# USBHUB.net
KiCad netlist of a schematic drawn in EasyEDA Pro
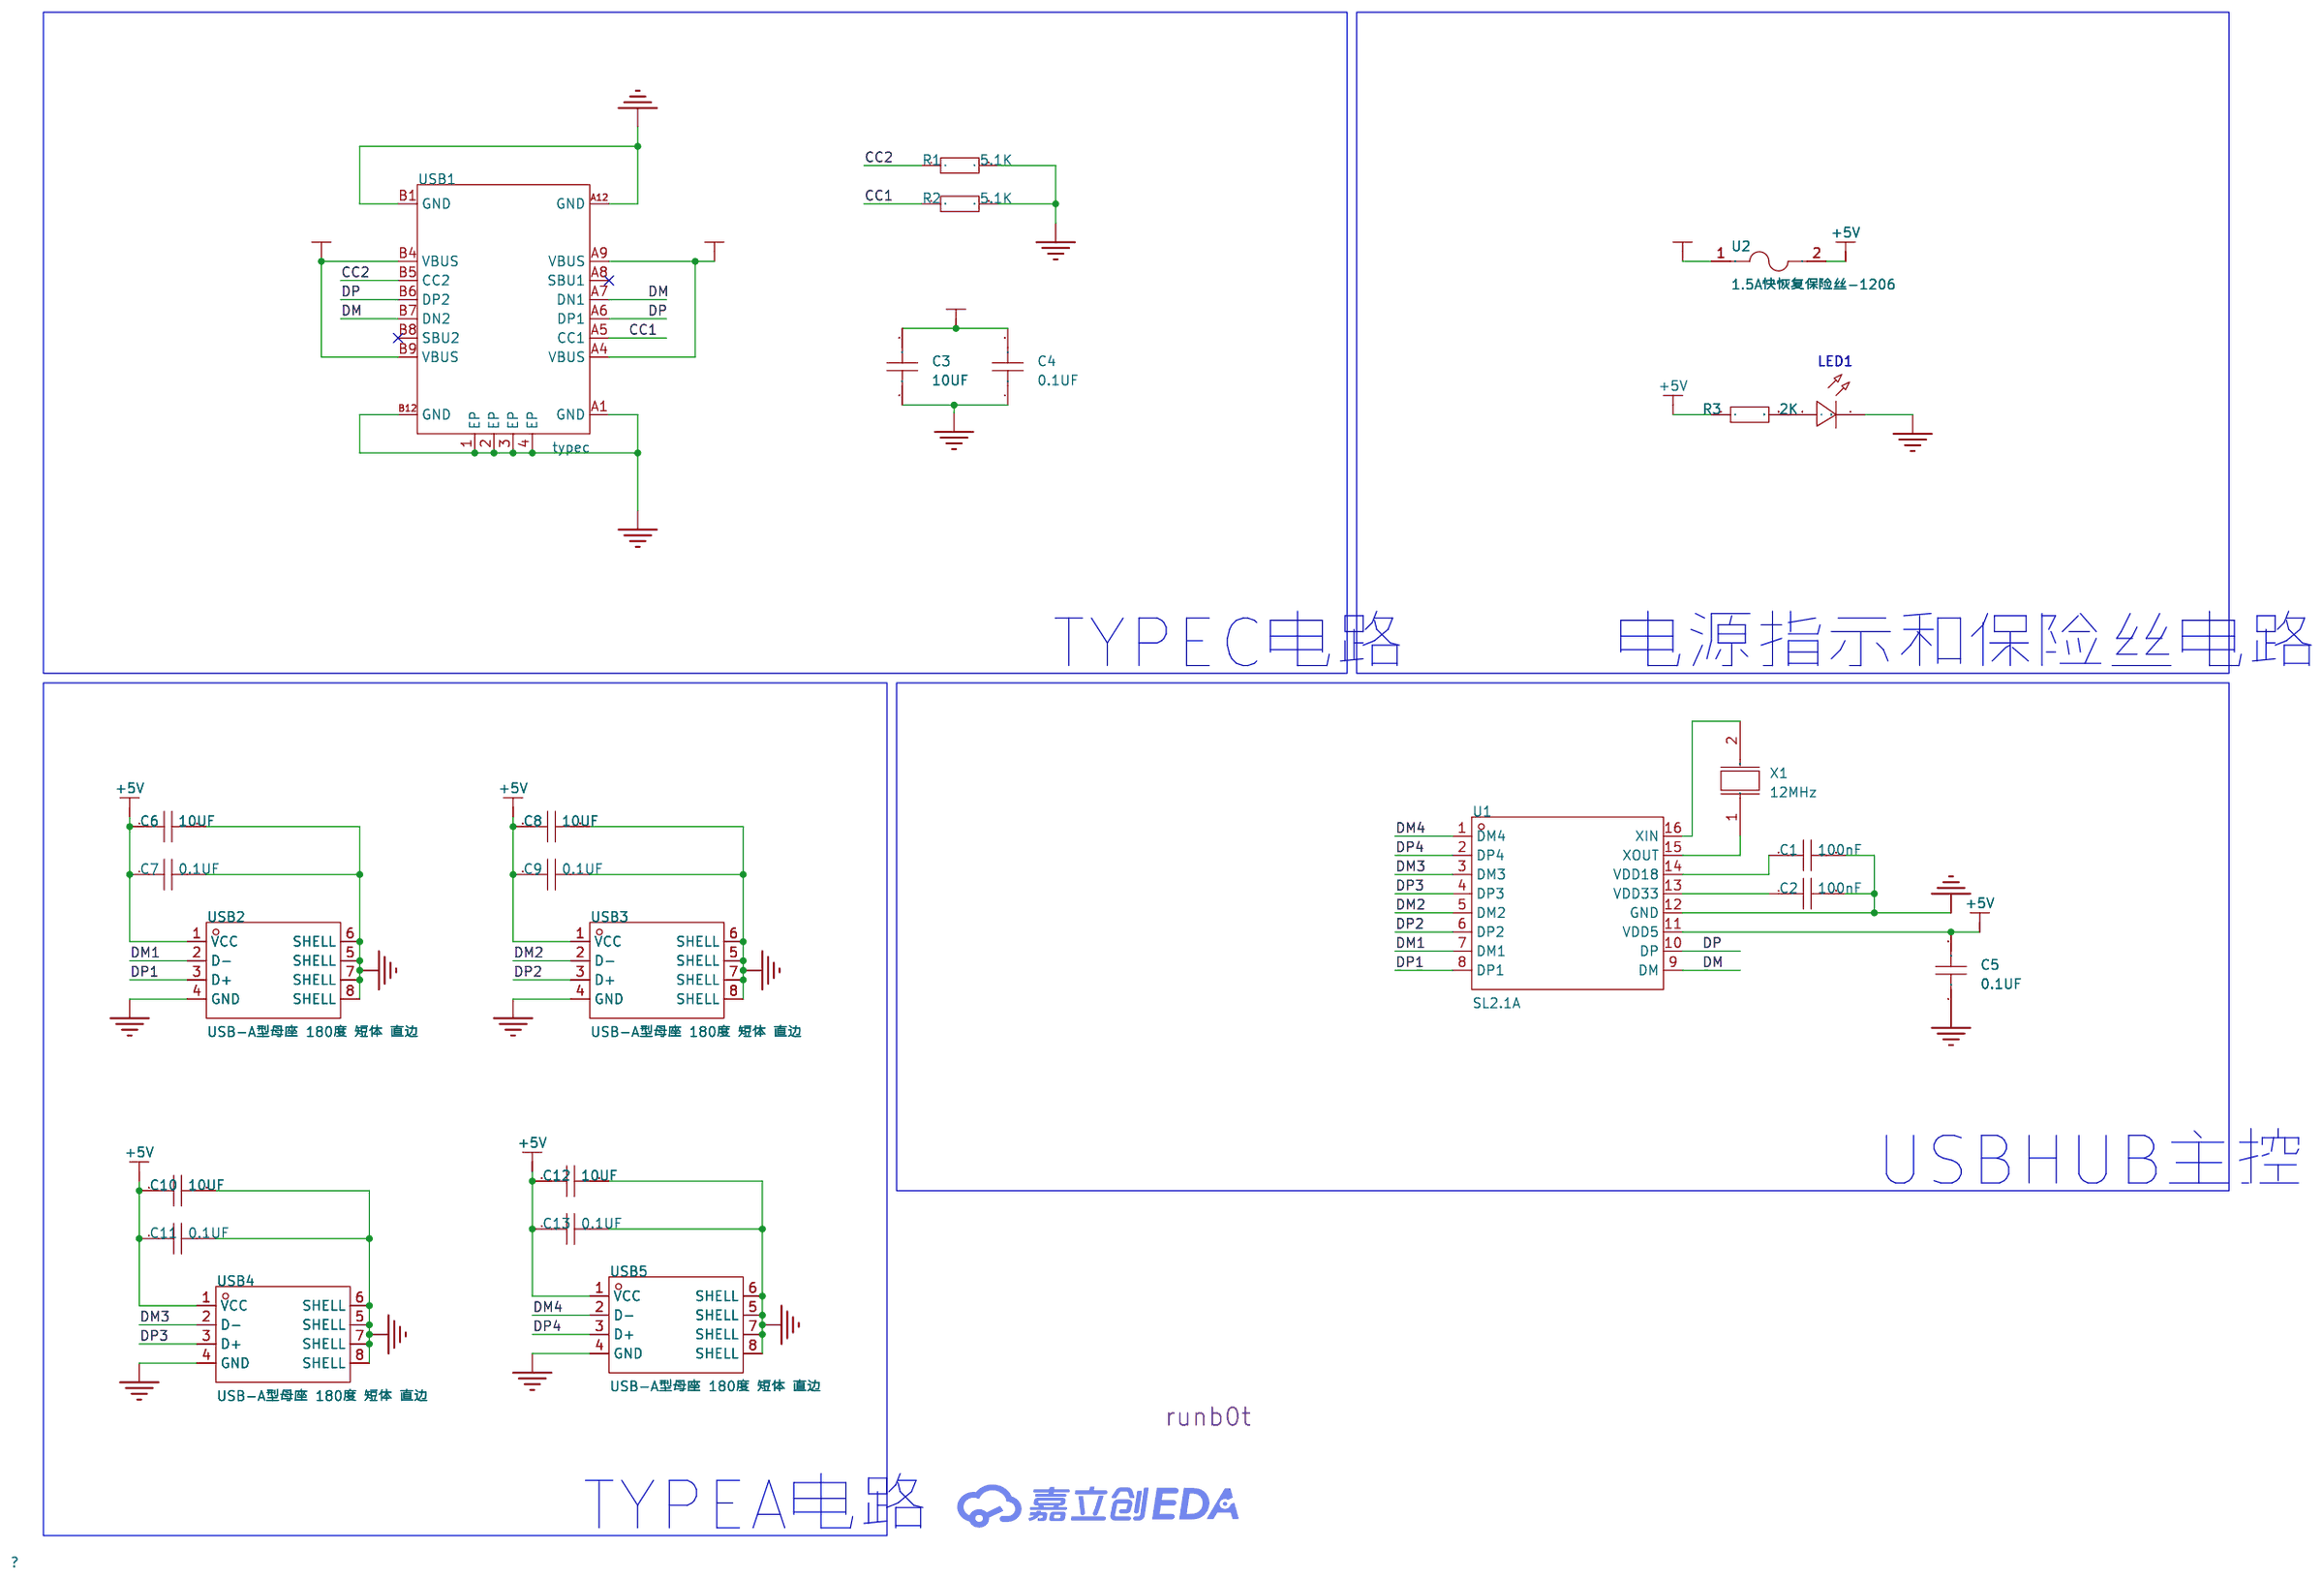
[diagram p0: schematic sheet]

(export (version "E")
  (design (tool "Eeschema 10.0.6"))
  (components
    (comp (ref "C1")
      (value "100nF")
      (footprint "easyedapro:C0805")
      (libsource (lib "easyedapro") (part "CapAcitance"))
    )
    (comp (ref "C2")
      (value "100nF")
      (footprint "easyedapro:C0805")
      (libsource (lib "easyedapro") (part "CapAcitance"))
    )
    (comp (ref "C3")
      (value "10UF")
      (footprint "easyedapro:C0805")
      (libsource (lib "easyedapro") (part "CapAcitance"))
    )
    (comp (ref "C4")
      (value "0.1UF")
      (footprint "easyedapro:C0805")
      (libsource (lib "easyedapro") (part "CapAcitance"))
    )
    (comp (ref "C5")
      (value "0.1UF")
      (footprint "easyedapro:C0805")
      (libsource (lib "easyedapro") (part "CapAcitance"))
    )
    (comp (ref "C6")
      (value "10UF")
      (footprint "easyedapro:C0805")
      (libsource (lib "easyedapro") (part "CapAcitance"))
    )
    (comp (ref "C7")
      (value "0.1UF")
      (footprint "easyedapro:C0805")
      (libsource (lib "easyedapro") (part "CapAcitance"))
    )
    (comp (ref "C8")
      (value "10UF")
      (footprint "easyedapro:C0805")
      (libsource (lib "easyedapro") (part "CapAcitance"))
    )
    (comp (ref "C9")
      (value "0.1UF")
      (footprint "easyedapro:C0805")
      (libsource (lib "easyedapro") (part "CapAcitance"))
    )
    (comp (ref "C10")
      (value "10UF")
      (footprint "easyedapro:C0805")
      (libsource (lib "easyedapro") (part "CapAcitance"))
    )
    (comp (ref "C11")
      (value "0.1UF")
      (footprint "easyedapro:C0805")
      (libsource (lib "easyedapro") (part "CapAcitance"))
    )
    (comp (ref "C12")
      (value "10UF")
      (footprint "easyedapro:C0805")
      (libsource (lib "easyedapro") (part "CapAcitance"))
    )
    (comp (ref "C13")
      (value "0.1UF")
      (footprint "easyedapro:C0805")
      (libsource (lib "easyedapro") (part "CapAcitance"))
    )
    (comp (ref "LED1")
      (value "~")
      (footprint "easyedapro:LED_0805")
      (libsource (lib "easyedapro") (part "LED_G"))
    )
    (comp (ref "R1") (value "5.1K") (footprint "easyedapro:R0805") (libsource (lib "easyedapro") (part "电阻")))
    (comp (ref "R2") (value "5.1K") (footprint "easyedapro:R0805") (libsource (lib "easyedapro") (part "电阻")))
    (comp (ref "R3") (value "2K") (footprint "easyedapro:R0805") (libsource (lib "easyedapro") (part "电阻")))
    (comp (ref "U1")
      (value "SL2.1A")
      (footprint "easyedapro:SOP-16_L10.0-W3.9-P1.27-LS6.0-BL")
      (description "SL2.1A是一颗高集成度,高性能,低功耗的USB2.0集线器主控芯片，支持USB2.0高速(480MHz),全速(12MHz)和低速模式(1.5MHz)，内置12MHz晶体振荡器。")
      (fields (field (name "Manufacturer") "CoreChips(和芯润德)"))
      (libsource (lib "easyedapro") (part "SL2.1A"))
    )
    (comp (ref "U2")
      (value "1.5A快恢复保险丝-1206")
      (footprint "easyedapro:F1206")
      (libsource (lib "easyedapro") (part "1.5A快恢复保险丝-1206"))
    )
    (comp (ref "USB1")
      (value "typec")
      (footprint "easyedapro:USB-C-SMD_KH-TYPE-C-16P")
      (libsource (lib "easyedapro") (part "TYPEC_C9900016956"))
    )
    (comp (ref "USB2")
      (value "USB-A型母座 180度 短体 直边")
      (footprint "easyedapro:USB-A-SMD_WT_C9900004571")
      (libsource (lib "easyedapro") (part "USB-A型母座 180度 短体 直边"))
    )
    (comp (ref "USB3")
      (value "USB-A型母座 180度 短体 直边")
      (footprint "easyedapro:USB-A-SMD_WT_C9900004571")
      (libsource (lib "easyedapro") (part "USB-A型母座 180度 短体 直边"))
    )
    (comp (ref "USB4")
      (value "USB-A型母座 180度 短体 直边")
      (footprint "easyedapro:USB-A-SMD_WT_C9900004571")
      (libsource (lib "easyedapro") (part "USB-A型母座 180度 短体 直边"))
    )
    (comp (ref "USB5")
      (value "USB-A型母座 180度 短体 直边")
      (footprint "easyedapro:USB-A-SMD_WT_C9900004571")
      (libsource (lib "easyedapro") (part "USB-A型母座 180度 短体 直边"))
    )
    (comp (ref "X1")
      (value "12MHz")
      (footprint "easyedapro:CRYSTAL-SMD_L5.0-W3.2-1-A")
      (description "晶振类型:贴片晶振;频率:12MHz;常温频差:±20ppm;外接负载电容:20pF;")
      (fields (field (name "Manufacturer Part") "G5312000202090") (field (name "Manufacturer") "JGHC(晶光华)"))
      (libsource (lib "easyedapro") (part "G5312000202090"))
    )
  )
  (nets
    (net (code "1") (name "+5V") (class "Default")
      (node (ref "C10") (pin "1") (pinfunction "1_1") (pintype "input"))
      (node (ref "C11") (pin "1") (pinfunction "1_1") (pintype "input"))
      (node (ref "C12") (pin "1") (pinfunction "1_1") (pintype "input"))
      (node (ref "C13") (pin "1") (pinfunction "1_1") (pintype "input"))
      (node (ref "C5") (pin "2") (pinfunction "2_2") (pintype "input"))
      (node (ref "C6") (pin "1") (pinfunction "1_1") (pintype "input"))
      (node (ref "C7") (pin "1") (pinfunction "1_1") (pintype "input"))
      (node (ref "C8") (pin "1") (pinfunction "1_1") (pintype "input"))
      (node (ref "C9") (pin "1") (pinfunction "1_1") (pintype "input"))
      (node (ref "R3") (pin "1") (pinfunction "1_1") (pintype "input"))
      (node (ref "U1") (pin "11") (pinfunction "VDD5_11") (pintype "unspecified"))
      (node (ref "U2") (pin "2") (pinfunction "2_2") (pintype "unspecified"))
      (node (ref "USB2") (pin "1") (pinfunction "VCC_1") (pintype "unspecified"))
      (node (ref "USB3") (pin "1") (pinfunction "VCC_1") (pintype "unspecified"))
      (node (ref "USB4") (pin "1") (pinfunction "VCC_1") (pintype "unspecified"))
      (node (ref "USB5") (pin "1") (pinfunction "VCC_1") (pintype "unspecified"))
    )
    (net (code "2") (name "/CC1") (class "Default")
      (node (ref "R2") (pin "1") (pinfunction "1_1") (pintype "input"))
      (node (ref "USB1") (pin "A5") (pinfunction "CC1_A5") (pintype "unspecified"))
    )
    (net (code "3") (name "/CC2") (class "Default")
      (node (ref "R1") (pin "1") (pinfunction "1_1") (pintype "input"))
      (node (ref "USB1") (pin "B5") (pinfunction "CC2_B5") (pintype "unspecified"))
    )
    (net (code "4") (name "/DM") (class "Default")
      (node (ref "U1") (pin "9") (pinfunction "DM_9") (pintype "unspecified"))
      (node (ref "USB1") (pin "A7") (pinfunction "DN1_A7") (pintype "unspecified"))
      (node (ref "USB1") (pin "B7") (pinfunction "DN2_B7") (pintype "unspecified"))
    )
    (net (code "5") (name "/DM1") (class "Default")
      (node (ref "U1") (pin "7") (pinfunction "DM1_7") (pintype "unspecified"))
      (node (ref "USB2") (pin "2") (pinfunction "D-_2") (pintype "unspecified"))
    )
    (net (code "6") (name "/DM2") (class "Default")
      (node (ref "U1") (pin "5") (pinfunction "DM2_5") (pintype "unspecified"))
      (node (ref "USB3") (pin "2") (pinfunction "D-_2") (pintype "unspecified"))
    )
    (net (code "7") (name "/DM3") (class "Default")
      (node (ref "U1") (pin "3") (pinfunction "DM3_3") (pintype "unspecified"))
      (node (ref "USB4") (pin "2") (pinfunction "D-_2") (pintype "unspecified"))
    )
    (net (code "8") (name "/DM4") (class "Default")
      (node (ref "U1") (pin "1") (pinfunction "DM4_1") (pintype "unspecified"))
      (node (ref "USB5") (pin "2") (pinfunction "D-_2") (pintype "unspecified"))
    )
    (net (code "9") (name "/DP") (class "Default")
      (node (ref "U1") (pin "10") (pinfunction "DP_10") (pintype "unspecified"))
      (node (ref "USB1") (pin "A6") (pinfunction "DP1_A6") (pintype "unspecified"))
      (node (ref "USB1") (pin "B6") (pinfunction "DP2_B6") (pintype "unspecified"))
    )
    (net (code "10") (name "/DP1") (class "Default")
      (node (ref "U1") (pin "8") (pinfunction "DP1_8") (pintype "unspecified"))
      (node (ref "USB2") (pin "3") (pinfunction "D+_3") (pintype "unspecified"))
    )
    (net (code "11") (name "/DP2") (class "Default")
      (node (ref "U1") (pin "6") (pinfunction "DP2_6") (pintype "unspecified"))
      (node (ref "USB3") (pin "3") (pinfunction "D+_3") (pintype "unspecified"))
    )
    (net (code "12") (name "/DP3") (class "Default")
      (node (ref "U1") (pin "4") (pinfunction "DP3_4") (pintype "unspecified"))
      (node (ref "USB4") (pin "3") (pinfunction "D+_3") (pintype "unspecified"))
    )
    (net (code "13") (name "/DP4") (class "Default")
      (node (ref "U1") (pin "2") (pinfunction "DP4_2") (pintype "unspecified"))
      (node (ref "USB5") (pin "3") (pinfunction "D+_3") (pintype "unspecified"))
    )
    (net (code "14") (name "GND") (class "Default")
      (node (ref "C1") (pin "2") (pinfunction "2_2") (pintype "input"))
      (node (ref "C10") (pin "2") (pinfunction "2_2") (pintype "input"))
      (node (ref "C11") (pin "2") (pinfunction "2_2") (pintype "input"))
      (node (ref "C12") (pin "2") (pinfunction "2_2") (pintype "input"))
      (node (ref "C13") (pin "2") (pinfunction "2_2") (pintype "input"))
      (node (ref "C2") (pin "2") (pinfunction "2_2") (pintype "input"))
      (node (ref "C3") (pin "1") (pinfunction "1_1") (pintype "input"))
      (node (ref "C4") (pin "1") (pinfunction "1_1") (pintype "input"))
      (node (ref "C5") (pin "1") (pinfunction "1_1") (pintype "input"))
      (node (ref "C6") (pin "2") (pinfunction "2_2") (pintype "input"))
      (node (ref "C7") (pin "2") (pinfunction "2_2") (pintype "input"))
      (node (ref "C8") (pin "2") (pinfunction "2_2") (pintype "input"))
      (node (ref "C9") (pin "2") (pinfunction "2_2") (pintype "input"))
      (node (ref "LED1") (pin "1") (pinfunction "C_1") (pintype "input"))
      (node (ref "R1") (pin "2") (pinfunction "2_2") (pintype "input"))
      (node (ref "R2") (pin "2") (pinfunction "2_2") (pintype "input"))
      (node (ref "U1") (pin "12") (pinfunction "GND_12") (pintype "unspecified"))
      (node (ref "USB1") (pin "1") (pinfunction "EP_1") (pintype "unspecified"))
      (node (ref "USB1") (pin "2") (pinfunction "EP_2") (pintype "unspecified"))
      (node (ref "USB1") (pin "3") (pinfunction "EP_3") (pintype "unspecified"))
      (node (ref "USB1") (pin "4") (pinfunction "EP_4") (pintype "unspecified"))
      (node (ref "USB1") (pin "A1") (pinfunction "GND_A1") (pintype "unspecified"))
      (node (ref "USB1") (pin "A12") (pinfunction "GND_A12") (pintype "unspecified"))
      (node (ref "USB1") (pin "B1") (pinfunction "GND_B1") (pintype "unspecified"))
      (node (ref "USB1") (pin "B12") (pinfunction "GND_B12") (pintype "unspecified"))
      (node (ref "USB2") (pin "4") (pinfunction "GND_4") (pintype "unspecified"))
      (node (ref "USB2") (pin "5") (pinfunction "SHELL_5") (pintype "unspecified"))
      (node (ref "USB2") (pin "6") (pinfunction "SHELL_6") (pintype "unspecified"))
      (node (ref "USB2") (pin "7") (pinfunction "SHELL_7") (pintype "unspecified"))
      (node (ref "USB2") (pin "8") (pinfunction "SHELL_8") (pintype "unspecified"))
      (node (ref "USB3") (pin "4") (pinfunction "GND_4") (pintype "unspecified"))
      (node (ref "USB3") (pin "5") (pinfunction "SHELL_5") (pintype "unspecified"))
      (node (ref "USB3") (pin "6") (pinfunction "SHELL_6") (pintype "unspecified"))
      (node (ref "USB3") (pin "7") (pinfunction "SHELL_7") (pintype "unspecified"))
      (node (ref "USB3") (pin "8") (pinfunction "SHELL_8") (pintype "unspecified"))
      (node (ref "USB4") (pin "4") (pinfunction "GND_4") (pintype "unspecified"))
      (node (ref "USB4") (pin "5") (pinfunction "SHELL_5") (pintype "unspecified"))
      (node (ref "USB4") (pin "6") (pinfunction "SHELL_6") (pintype "unspecified"))
      (node (ref "USB4") (pin "7") (pinfunction "SHELL_7") (pintype "unspecified"))
      (node (ref "USB4") (pin "8") (pinfunction "SHELL_8") (pintype "unspecified"))
      (node (ref "USB5") (pin "4") (pinfunction "GND_4") (pintype "unspecified"))
      (node (ref "USB5") (pin "5") (pinfunction "SHELL_5") (pintype "unspecified"))
      (node (ref "USB5") (pin "6") (pinfunction "SHELL_6") (pintype "unspecified"))
      (node (ref "USB5") (pin "7") (pinfunction "SHELL_7") (pintype "unspecified"))
      (node (ref "USB5") (pin "8") (pinfunction "SHELL_8") (pintype "unspecified"))
    )
    (net (code "15") (name "Net-(LED1-A)") (class "Default")
      (node (ref "LED1") (pin "2") (pinfunction "A_2") (pintype "input"))
      (node (ref "R3") (pin "2") (pinfunction "2_2") (pintype "input"))
    )
    (net (code "16") (name "Net-(U1-VDD18)") (class "Default")
      (node (ref "C1") (pin "1") (pinfunction "1_1") (pintype "input"))
      (node (ref "U1") (pin "14") (pinfunction "VDD18_14") (pintype "unspecified"))
    )
    (net (code "17") (name "Net-(U1-VDD33)") (class "Default")
      (node (ref "C2") (pin "1") (pinfunction "1_1") (pintype "input"))
      (node (ref "U1") (pin "13") (pinfunction "VDD33_13") (pintype "unspecified"))
    )
    (net (code "18") (name "Net-(U1-XIN)") (class "Default")
      (node (ref "U1") (pin "16") (pinfunction "XIN_16") (pintype "unspecified"))
      (node (ref "X1") (pin "2") (pinfunction "2_2") (pintype "unspecified"))
    )
    (net (code "19") (name "Net-(U1-XOUT)") (class "Default")
      (node (ref "U1") (pin "15") (pinfunction "XOUT_15") (pintype "unspecified"))
      (node (ref "X1") (pin "1") (pinfunction "1_1") (pintype "unspecified"))
    )
    (net (code "20") (name "VCC+5V") (class "Default")
      (node (ref "C3") (pin "2") (pinfunction "2_2") (pintype "input"))
      (node (ref "C4") (pin "2") (pinfunction "2_2") (pintype "input"))
      (node (ref "U2") (pin "1") (pinfunction "1_1") (pintype "unspecified"))
      (node (ref "USB1") (pin "A4") (pinfunction "VBUS_A4") (pintype "unspecified"))
      (node (ref "USB1") (pin "A9") (pinfunction "VBUS_A9") (pintype "unspecified"))
      (node (ref "USB1") (pin "B4") (pinfunction "VBUS_B4") (pintype "unspecified"))
      (node (ref "USB1") (pin "B9") (pinfunction "VBUS_B9") (pintype "unspecified"))
    )
    (net (code "21") (name "unconnected-(USB1-SBU1-PadA8)") (class "Default")
      (node (ref "USB1") (pin "A8") (pinfunction "SBU1_A8") (pintype "unspecified+no_connect"))
    )
    (net (code "22") (name "unconnected-(USB1-SBU2-PadB8)") (class "Default")
      (node (ref "USB1") (pin "B8") (pinfunction "SBU2_B8") (pintype "unspecified+no_connect"))
    )
  )
)
